# AstableMultivibrator-NPN-CapPol.net
KiCad netlist of a schematic drawn in EAGLE
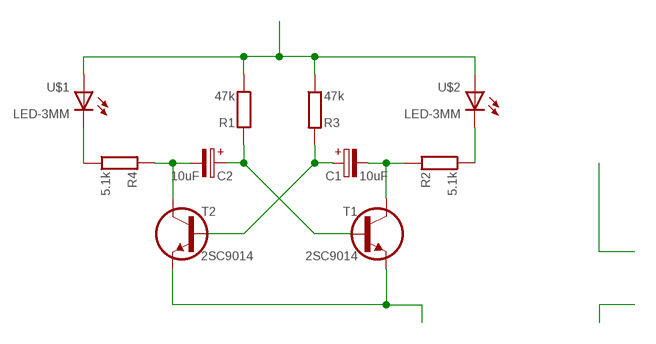
[diagram p0: schematic, sheet 1]

(export (version "E")
  (design (tool "Eeschema 10.0.6"))
  (components
    (comp (ref "C1")
      (value "10uF")
      (footprint "eagle-import:E2,5-4")
      (libsource (lib "eagle-import") (part "CPOL-HE2,5-4"))
    )
    (comp (ref "C2")
      (value "10uF")
      (footprint "eagle-import:E2,5-4")
      (libsource (lib "eagle-import") (part "CPOL-HE2,5-4"))
    )
    (comp (ref "R1")
      (value "47k")
      (footprint "eagle-import:0202_7-V")
      (libsource (lib "eagle-import") (part "R0202/7-V"))
    )
    (comp (ref "R2")
      (value "5.1k")
      (footprint "eagle-import:0202_7-V")
      (libsource (lib "eagle-import") (part "R0202/7-V"))
    )
    (comp (ref "R3")
      (value "47k")
      (footprint "eagle-import:0202_7-V")
      (libsource (lib "eagle-import") (part "R0202/7-V"))
    )
    (comp (ref "R4")
      (value "5.1k")
      (footprint "eagle-import:0202_7-V")
      (libsource (lib "eagle-import") (part "R0202/7-V"))
    )
    (comp (ref "T1")
      (value "2SC9014")
      (footprint "eagle-import:TO92-EBC")
      (libsource (lib "eagle-import") (part "2SC9014"))
    )
    (comp (ref "T2")
      (value "2SC9014")
      (footprint "eagle-import:TO92-EBC")
      (libsource (lib "eagle-import") (part "2SC9014"))
    )
    (comp (ref "U$1")
      (value "LED-3MM")
      (footprint "eagle-import:LED_3MM")
      (libsource (lib "eagle-import") (part "LED-3MM"))
    )
    (comp (ref "U$2")
      (value "LED-3MM")
      (footprint "eagle-import:LED_3MM")
      (libsource (lib "eagle-import") (part "LED-3MM"))
    )
  )
  (nets
    (net (code "1") (name "Net-(R1-1)") (class "Default")
      (node (ref "C2") (pin "+") (pinfunction "+_+") (pintype "passive"))
      (node (ref "R1") (pin "2") (pinfunction "1_2") (pintype "passive"))
      (node (ref "T1") (pin "B") (pinfunction "B_B") (pintype "passive"))
    )
    (net (code "2") (name "Net-(R1-2)") (class "Default")
      (node (ref "R1") (pin "1") (pinfunction "2_1") (pintype "passive"))
      (node (ref "R3") (pin "1") (pinfunction "2_1") (pintype "passive"))
      (node (ref "U$1") (pin "A") (pinfunction "A_A") (pintype "passive"))
      (node (ref "U$2") (pin "A") (pinfunction "A_A") (pintype "passive"))
    )
    (net (code "3") (name "Net-(R2-1)") (class "Default")
      (node (ref "C1") (pin "-") (pinfunction "-_-") (pintype "passive"))
      (node (ref "R2") (pin "2") (pinfunction "1_2") (pintype "passive"))
      (node (ref "T1") (pin "C") (pinfunction "C_C") (pintype "passive"))
    )
    (net (code "4") (name "Net-(R2-2)") (class "Default")
      (node (ref "R2") (pin "1") (pinfunction "2_1") (pintype "passive"))
      (node (ref "U$2") (pin "K") (pinfunction "C_K") (pintype "passive"))
    )
    (net (code "5") (name "Net-(R3-1)") (class "Default")
      (node (ref "C1") (pin "+") (pinfunction "+_+") (pintype "passive"))
      (node (ref "R3") (pin "2") (pinfunction "1_2") (pintype "passive"))
      (node (ref "T2") (pin "B") (pinfunction "B_B") (pintype "passive"))
    )
    (net (code "6") (name "Net-(R4-1)") (class "Default")
      (node (ref "C2") (pin "-") (pinfunction "-_-") (pintype "passive"))
      (node (ref "R4") (pin "2") (pinfunction "1_2") (pintype "passive"))
      (node (ref "T2") (pin "C") (pinfunction "C_C") (pintype "passive"))
    )
    (net (code "7") (name "Net-(R4-2)") (class "Default")
      (node (ref "R4") (pin "1") (pinfunction "2_1") (pintype "passive"))
      (node (ref "U$1") (pin "K") (pinfunction "C_K") (pintype "passive"))
    )
    (net (code "8") (name "Net-(T1-PadE)") (class "Default")
      (node (ref "T1") (pin "E") (pinfunction "E_E") (pintype "passive"))
      (node (ref "T2") (pin "E") (pinfunction "E_E") (pintype "passive"))
    )
  )
)
